# CP_Sapling.net
KiCad netlist of a schematic drawn in EAGLE
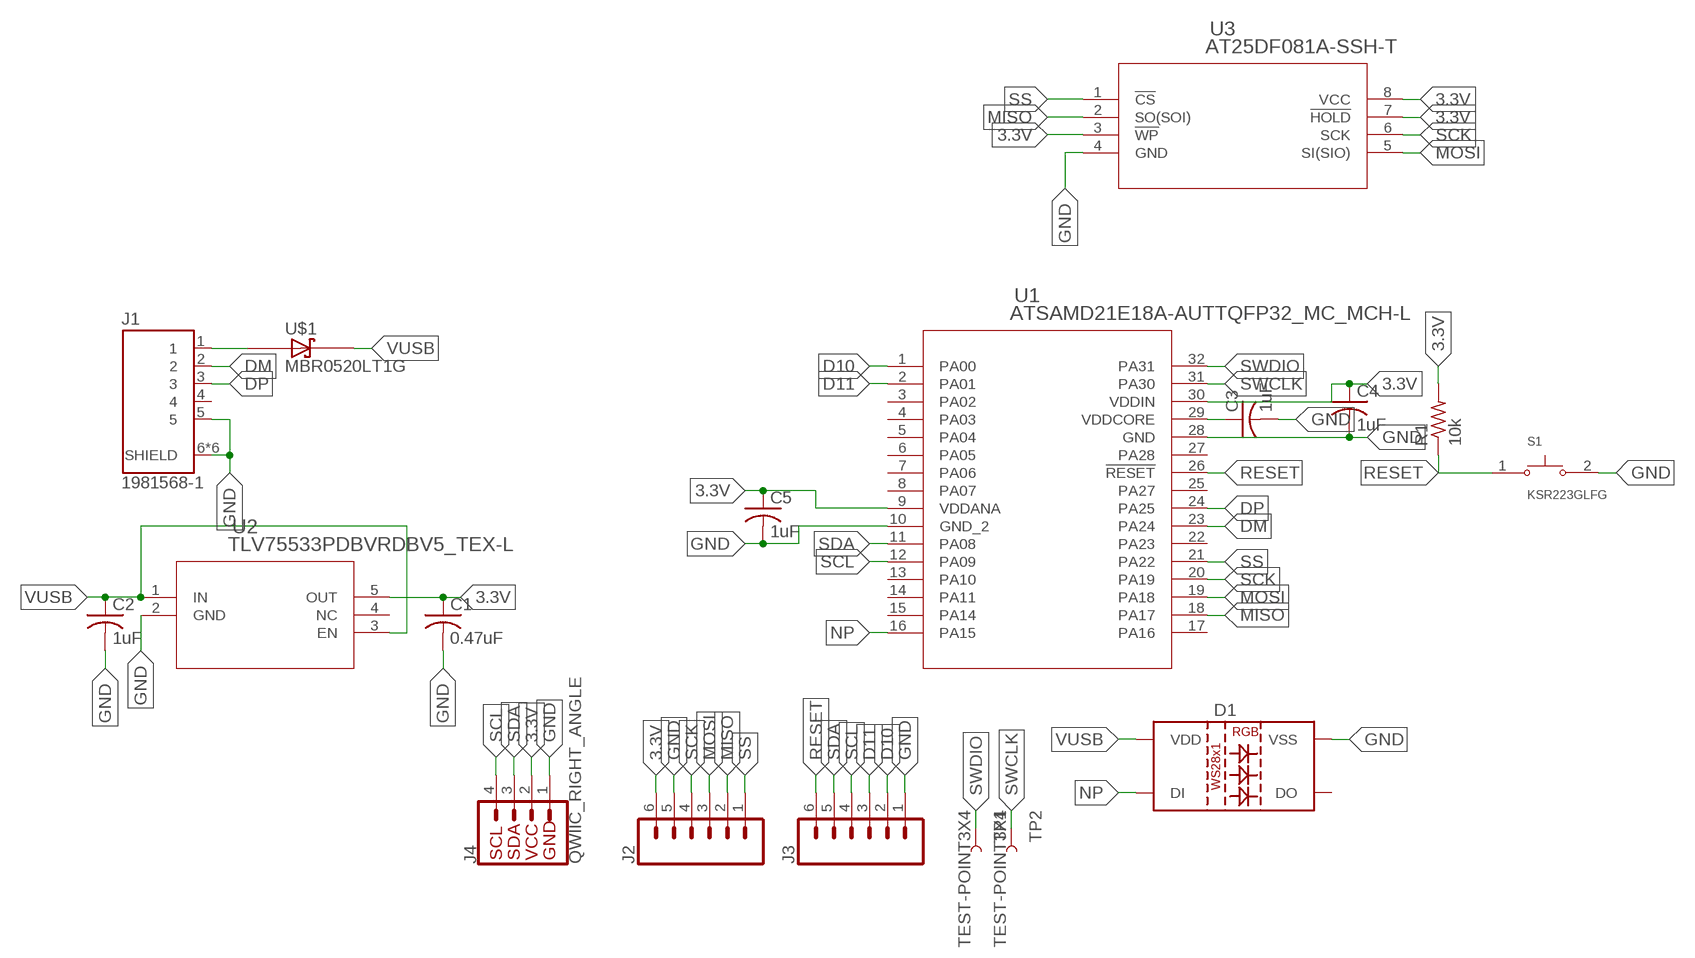
[diagram p0: schematic, sheet 1]

(export (version "E")
  (design (tool "Eeschema 10.0.6"))
  (components
    (comp (ref "C1")
      (value "0.47uF")
      (footprint "eagle-import:C0402")
      (libsource (lib "eagle-import") (part "C-USC0402"))
    )
    (comp (ref "C2")
      (value "1uF")
      (footprint "eagle-import:C0402")
      (libsource (lib "eagle-import") (part "C-USC0402"))
    )
    (comp (ref "C3")
      (value "1uF")
      (footprint "eagle-import:C0402")
      (libsource (lib "eagle-import") (part "C-USC0402"))
    )
    (comp (ref "C4")
      (value "1uF")
      (footprint "eagle-import:C0402")
      (libsource (lib "eagle-import") (part "C-USC0402"))
    )
    (comp (ref "C5")
      (value "1uF")
      (footprint "eagle-import:C0402")
      (libsource (lib "eagle-import") (part "C-USC0402"))
    )
    (comp (ref "D1")
      (value "WS2812B")
      (footprint "eagle-import:WS2812B-3535")
      (libsource (lib "eagle-import") (part "WS2812BWS2812B-3535"))
    )
    (comp (ref "J1")
      (value "1981568-1")
      (footprint "eagle-import:TE_1981568-1")
      (fields (field (name "MF") "TE Connectivity") (field (name "MP") "19815681"))
      (libsource (lib "eagle-import") (part "1981568-1"))
    )
    (comp (ref "J2")
      (value "CONN_06NO_SILK_NO_POP")
      (footprint "eagle-import:1X06_NO_SILK")
      (libsource (lib "eagle-import") (part "CONN_06NO_SILK_NO_POP"))
    )
    (comp (ref "J3")
      (value "CONN_06NO_SILK_NO_POP")
      (footprint "eagle-import:1X06_NO_SILK")
      (libsource (lib "eagle-import") (part "CONN_06NO_SILK_NO_POP"))
    )
    (comp (ref "J4")
      (value "QWIIC_RIGHT_ANGLE")
      (footprint "eagle-import:JST04_1MM_RA")
      (libsource (lib "eagle-import") (part "QWIIC_CONNECTORJS-1MM"))
    )
    (comp (ref "R1")
      (value "10k")
      (footprint "eagle-import:R0402")
      (libsource (lib "eagle-import") (part "R-US_R0402"))
    )
    (comp (ref "S1")
      (value "KSR223GLFG")
      (footprint "eagle-import:SW_KSR223GLFG")
      (fields (field (name "MF") "C&K"))
      (libsource (lib "eagle-import") (part "KSR223GLFG"))
    )
    (comp (ref "TP1")
      (value "TEST-POINT3X4")
      (footprint "eagle-import:PAD.03X.04")
      (libsource (lib "eagle-import") (part "TEST-POINT3X4"))
    )
    (comp (ref "TP2")
      (value "TEST-POINT3X4")
      (footprint "eagle-import:PAD.03X.04")
      (libsource (lib "eagle-import") (part "TEST-POINT3X4"))
    )
    (comp (ref "U$1")
      (value "MBR0520LT1G")
      (footprint "eagle-import:SOD3716X117(SOD-123)")
      (fields (field (name "MF") "ON Semiconductor"))
      (libsource (lib "eagle-import") (part "MBR0520LT1G"))
    )
    (comp (ref "U1")
      (value "ATSAMD21E18A-AUTTQFP32_MC_MCH-L")
      (footprint "eagle-import:TQFP32_MC_MCH-L")
      (fields
        (field (name "MANUFACTURER_PART_NUMBER") "ATSAMD21E18A-AUT")
        (field (name "COPYRIGHT") "Copyright (C) 2018 Accelerated Designs. All rights reserved")
      )
      (libsource (lib "eagle-import") (part "ATSAMD21E18A-AUTTQFP32_MC_MCH-L"))
    )
    (comp (ref "U2")
      (value "TLV75533PDBVRDBV5_TEX-L")
      (footprint "eagle-import:DBV5_TEX-L")
      (fields
        (field (name "MANUFACTURER_PART_NUMBER") "TLV75533PDBVR")
        (field (name "COPYRIGHT") "Copyright (C) 2018 Accelerated Designs. All rights reserved")
      )
      (libsource (lib "eagle-import") (part "TLV75533PDBVRDBV5_TEX-L"))
    )
    (comp (ref "U3")
      (value "AT25DF081A-SSH-T")
      (footprint "eagle-import:SOIC_AT25DF081_ADO")
      (fields (field (name "COPYRIGHT") "Copyright (C) 2018 Accelerated Designs. All rights reserved"))
      (libsource (lib "eagle-import") (part "AT25DF081A-SSH-T"))
    )
  )
  (nets
    (net (code "1") (name "3.3V") (class "Default")
      (node (ref "C1") (pin "1") (pinfunction "1_1") (pintype "passive"))
      (node (ref "C4") (pin "1") (pinfunction "1_1") (pintype "passive"))
      (node (ref "C5") (pin "1") (pinfunction "1_1") (pintype "passive"))
      (node (ref "J2") (pin "6") (pinfunction "6_6") (pintype "passive"))
      (node (ref "J4") (pin "2") (pinfunction "2_2") (pintype "power_in"))
      (node (ref "R1") (pin "2") (pinfunction "2_2") (pintype "passive"))
      (node (ref "U1") (pin "30") (pinfunction "VDDIN_30") (pintype "power_in"))
      (node (ref "U1") (pin "9") (pinfunction "VDDANA_9") (pintype "power_in"))
      (node (ref "U2") (pin "5") (pinfunction "OUT_5") (pintype "output"))
      (node (ref "U3") (pin "3") (pinfunction "~{WP}_3") (pintype "input"))
      (node (ref "U3") (pin "7") (pinfunction "~{HOLD}_7") (pintype "input"))
      (node (ref "U3") (pin "8") (pinfunction "VCC_8") (pintype "power_in"))
    )
    (net (code "2") (name "D10") (class "Default")
      (node (ref "J3") (pin "2") (pinfunction "2_2") (pintype "passive"))
      (node (ref "U1") (pin "1") (pinfunction "PA00_1") (pintype "bidirectional"))
    )
    (net (code "3") (name "D11") (class "Default")
      (node (ref "J3") (pin "3") (pinfunction "3_3") (pintype "passive"))
      (node (ref "U1") (pin "2") (pinfunction "PA01_2") (pintype "bidirectional"))
    )
    (net (code "4") (name "DM") (class "Default")
      (node (ref "J1") (pin "2") (pinfunction "2_2") (pintype "passive"))
      (node (ref "U1") (pin "23") (pinfunction "PA24_23") (pintype "bidirectional"))
    )
    (net (code "5") (name "DP") (class "Default")
      (node (ref "J1") (pin "3") (pinfunction "3_3") (pintype "passive"))
      (node (ref "U1") (pin "24") (pinfunction "PA25_24") (pintype "bidirectional"))
    )
    (net (code "6") (name "GND") (class "Default")
      (node (ref "C1") (pin "2") (pinfunction "2_2") (pintype "passive"))
      (node (ref "C2") (pin "2") (pinfunction "2_2") (pintype "passive"))
      (node (ref "C3") (pin "2") (pinfunction "2_2") (pintype "passive"))
      (node (ref "C4") (pin "2") (pinfunction "2_2") (pintype "passive"))
      (node (ref "C5") (pin "2") (pinfunction "2_2") (pintype "passive"))
      (node (ref "D1") (pin "3") (pinfunction "VSS_3") (pintype "bidirectional"))
      (node (ref "J1") (pin "10") (pinfunction "SHIELD_10") (pintype "passive"))
      (node (ref "J1") (pin "11") (pinfunction "SHIELD_11") (pintype "passive"))
      (node (ref "J1") (pin "5") (pinfunction "5_5") (pintype "passive"))
      (node (ref "J1") (pin "6") (pinfunction "SHIELD_6") (pintype "passive"))
      (node (ref "J1") (pin "7") (pinfunction "SHIELD_7") (pintype "passive"))
      (node (ref "J1") (pin "8") (pinfunction "SHIELD_8") (pintype "passive"))
      (node (ref "J1") (pin "9") (pinfunction "SHIELD_9") (pintype "passive"))
      (node (ref "J2") (pin "5") (pinfunction "5_5") (pintype "passive"))
      (node (ref "J3") (pin "1") (pinfunction "1_1") (pintype "passive"))
      (node (ref "J4") (pin "1") (pinfunction "1_1") (pintype "power_in"))
      (node (ref "S1") (pin "2") (pinfunction "2_2") (pintype "passive"))
      (node (ref "U1") (pin "10") (pinfunction "GND_2_10") (pintype "passive"))
      (node (ref "U1") (pin "28") (pinfunction "GND_28") (pintype "passive"))
      (node (ref "U2") (pin "2") (pinfunction "GND_2") (pintype "power_in"))
      (node (ref "U3") (pin "4") (pinfunction "GND_4") (pintype "power_in"))
    )
    (net (code "7") (name "MISO") (class "Default")
      (node (ref "J2") (pin "2") (pinfunction "2_2") (pintype "passive"))
      (node (ref "U1") (pin "18") (pinfunction "PA17_18") (pintype "bidirectional"))
      (node (ref "U3") (pin "2") (pinfunction "SO(SOI)_2") (pintype "bidirectional"))
    )
    (net (code "8") (name "MOSI") (class "Default")
      (node (ref "J2") (pin "3") (pinfunction "3_3") (pintype "passive"))
      (node (ref "U1") (pin "19") (pinfunction "PA18_19") (pintype "bidirectional"))
      (node (ref "U3") (pin "5") (pinfunction "SI(SIO)_5") (pintype "bidirectional"))
    )
    (net (code "9") (name "NP") (class "Default")
      (node (ref "D1") (pin "4") (pinfunction "DI_4") (pintype "bidirectional"))
      (node (ref "U1") (pin "16") (pinfunction "PA15_16") (pintype "bidirectional"))
    )
    (net (code "10") (name "Net-(U$1-A)") (class "Default")
      (node (ref "J1") (pin "1") (pinfunction "1_1") (pintype "passive"))
      (node (ref "U$1") (pin "2") (pinfunction "A_2") (pintype "passive"))
    )
    (net (code "11") (name "Net-(U1-VDDCORE)") (class "Default")
      (node (ref "C3") (pin "1") (pinfunction "1_1") (pintype "passive"))
      (node (ref "U1") (pin "29") (pinfunction "VDDCORE_29") (pintype "power_in"))
    )
    (net (code "12") (name "RESET") (class "Default")
      (node (ref "J3") (pin "6") (pinfunction "6_6") (pintype "passive"))
      (node (ref "R1") (pin "1") (pinfunction "1_1") (pintype "passive"))
      (node (ref "S1") (pin "1") (pinfunction "1_1") (pintype "passive"))
      (node (ref "U1") (pin "26") (pinfunction "~{RESET}_26") (pintype "passive"))
    )
    (net (code "13") (name "SCK") (class "Default")
      (node (ref "J2") (pin "4") (pinfunction "4_4") (pintype "passive"))
      (node (ref "U1") (pin "20") (pinfunction "PA19_20") (pintype "bidirectional"))
      (node (ref "U3") (pin "6") (pinfunction "SCK_6") (pintype "input"))
    )
    (net (code "14") (name "SCL") (class "Default")
      (node (ref "J3") (pin "4") (pinfunction "4_4") (pintype "passive"))
      (node (ref "J4") (pin "4") (pinfunction "4_4") (pintype "passive"))
      (node (ref "U1") (pin "12") (pinfunction "PA09_12") (pintype "bidirectional"))
    )
    (net (code "15") (name "SDA") (class "Default")
      (node (ref "J3") (pin "5") (pinfunction "5_5") (pintype "passive"))
      (node (ref "J4") (pin "3") (pinfunction "3_3") (pintype "passive"))
      (node (ref "U1") (pin "11") (pinfunction "PA08_11") (pintype "bidirectional"))
    )
    (net (code "16") (name "SS") (class "Default")
      (node (ref "J2") (pin "1") (pinfunction "1_1") (pintype "passive"))
      (node (ref "U1") (pin "21") (pinfunction "PA22_21") (pintype "bidirectional"))
      (node (ref "U3") (pin "1") (pinfunction "~{CS}_1") (pintype "input"))
    )
    (net (code "17") (name "SWCLK") (class "Default")
      (node (ref "TP2") (pin "P$1") (pinfunction "1_P$1") (pintype "bidirectional"))
      (node (ref "U1") (pin "31") (pinfunction "PA30_31") (pintype "bidirectional"))
    )
    (net (code "18") (name "SWDIO") (class "Default")
      (node (ref "TP1") (pin "P$1") (pinfunction "1_P$1") (pintype "bidirectional"))
      (node (ref "U1") (pin "32") (pinfunction "PA31_32") (pintype "bidirectional"))
    )
    (net (code "19") (name "VUSB") (class "Default")
      (node (ref "C2") (pin "1") (pinfunction "1_1") (pintype "passive"))
      (node (ref "D1") (pin "1") (pinfunction "VDD_1") (pintype "bidirectional"))
      (node (ref "U$1") (pin "1") (pinfunction "C_1") (pintype "passive"))
      (node (ref "U2") (pin "1") (pinfunction "IN_1") (pintype "input"))
      (node (ref "U2") (pin "3") (pinfunction "EN_3") (pintype "input"))
    )
    (net (code "20") (name "unconnected-(D1-DO-Pad2)") (class "Default")
      (node (ref "D1") (pin "2") (pinfunction "DO_2") (pintype "bidirectional"))
    )
    (net (code "21") (name "unconnected-(J1-Pad4)") (class "Default")
      (node (ref "J1") (pin "4") (pinfunction "4_4") (pintype "passive"))
    )
    (net (code "22") (name "unconnected-(U1-PA02-Pad3)") (class "Default")
      (node (ref "U1") (pin "3") (pinfunction "PA02_3") (pintype "bidirectional"))
    )
    (net (code "23") (name "unconnected-(U1-PA03-Pad4)") (class "Default")
      (node (ref "U1") (pin "4") (pinfunction "PA03_4") (pintype "bidirectional"))
    )
    (net (code "24") (name "unconnected-(U1-PA04-Pad5)") (class "Default")
      (node (ref "U1") (pin "5") (pinfunction "PA04_5") (pintype "bidirectional"))
    )
    (net (code "25") (name "unconnected-(U1-PA05-Pad6)") (class "Default")
      (node (ref "U1") (pin "6") (pinfunction "PA05_6") (pintype "bidirectional"))
    )
    (net (code "26") (name "unconnected-(U1-PA06-Pad7)") (class "Default")
      (node (ref "U1") (pin "7") (pinfunction "PA06_7") (pintype "bidirectional"))
    )
    (net (code "27") (name "unconnected-(U1-PA07-Pad8)") (class "Default")
      (node (ref "U1") (pin "8") (pinfunction "PA07_8") (pintype "bidirectional"))
    )
    (net (code "28") (name "unconnected-(U1-PA10-Pad13)") (class "Default")
      (node (ref "U1") (pin "13") (pinfunction "PA10_13") (pintype "bidirectional"))
    )
    (net (code "29") (name "unconnected-(U1-PA11-Pad14)") (class "Default")
      (node (ref "U1") (pin "14") (pinfunction "PA11_14") (pintype "bidirectional"))
    )
    (net (code "30") (name "unconnected-(U1-PA14-Pad15)") (class "Default")
      (node (ref "U1") (pin "15") (pinfunction "PA14_15") (pintype "bidirectional"))
    )
    (net (code "31") (name "unconnected-(U1-PA16-Pad17)") (class "Default")
      (node (ref "U1") (pin "17") (pinfunction "PA16_17") (pintype "bidirectional"))
    )
    (net (code "32") (name "unconnected-(U1-PA23-Pad22)") (class "Default")
      (node (ref "U1") (pin "22") (pinfunction "PA23_22") (pintype "bidirectional"))
    )
    (net (code "33") (name "unconnected-(U1-PA27-Pad25)") (class "Default")
      (node (ref "U1") (pin "25") (pinfunction "PA27_25") (pintype "bidirectional"))
    )
    (net (code "34") (name "unconnected-(U1-PA28-Pad27)") (class "Default")
      (node (ref "U1") (pin "27") (pinfunction "PA28_27") (pintype "bidirectional"))
    )
    (net (code "35") (name "unconnected-(U2-NC-Pad4)") (class "Default")
      (node (ref "U2") (pin "4") (pinfunction "NC_4") (pintype "no_connect"))
    )
  )
)
